# drv.net
KiCad netlist of a schematic drawn in Altium Designer
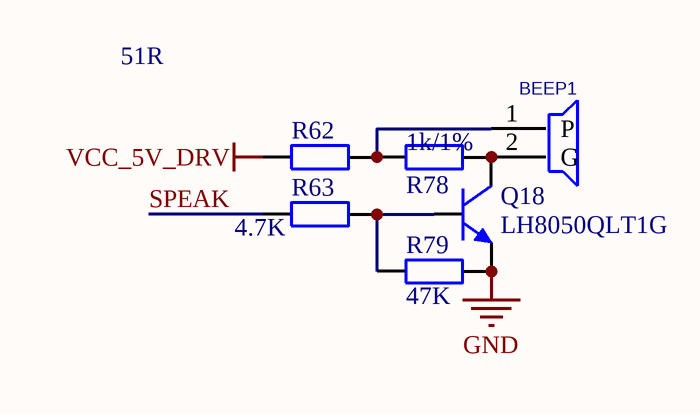
[diagram p0: drv.SchDoc]

(export (version "E")
  (design (tool "Eeschema 10.0.6"))
  (components
    (comp (ref "BEEP1")
      (value "BEEP-9.5X5.5")
      (footprint "BEEP-9.5X5.5")
      (libsource (lib "MINI-V3") (part "BEEP-9.5X5.5"))
    )
    (comp (ref "Q18")
      (value "LH8050QLT1G")
      (footprint "SOT-23")
      (description "NPN")
      (libsource (lib "XiaoyI") (part "NPN-1"))
    )
    (comp (ref "R62")
      (value "51R")
      (footprint "0603R")
      (description "贴片电阻 5%")
      (libsource (lib "") (part "RES0_1"))
    )
    (comp (ref "R63")
      (value "4.7K")
      (footprint "0603R")
      (description "贴片电阻 5%")
      (libsource (lib "ABB") (part "RES0"))
    )
    (comp (ref "R78")
      (value "1k/1%")
      (footprint "0603R")
      (description "贴片电阻 5%")
      (libsource (lib "") (part "RES0_1"))
    )
    (comp (ref "R79")
      (value "47K")
      (footprint "0603R")
      (description "贴片电阻 5%")
      (libsource (lib "ABB") (part "RES0"))
    )
  )
  (nets
    (net (code "1") (name "/SPEAK") (class "Default")
      (node (ref "R63") (pin "1") (pinfunction "1_1") (pintype "passive"))
    )
    (net (code "2") (name "GND") (class "Default")
      (node (ref "Q18") (pin "2") (pinfunction "E_2") (pintype "passive"))
      (node (ref "R79") (pin "2") (pinfunction "2_2") (pintype "passive"))
    )
    (net (code "3") (name "Net-(BEEP1-G)") (class "Default")
      (node (ref "BEEP1") (pin "2") (pinfunction "G_2") (pintype "passive"))
      (node (ref "Q18") (pin "3") (pinfunction "C_3") (pintype "passive"))
      (node (ref "R78") (pin "1") (pinfunction "1_1") (pintype "passive"))
    )
    (net (code "4") (name "Net-(BEEP1-P)") (class "Default")
      (node (ref "BEEP1") (pin "1") (pinfunction "P_1") (pintype "passive"))
      (node (ref "R62") (pin "1") (pinfunction "1_1") (pintype "passive"))
      (node (ref "R78") (pin "2") (pinfunction "2_2") (pintype "passive"))
    )
    (net (code "5") (name "Net-(Q18-B)") (class "Default")
      (node (ref "Q18") (pin "1") (pinfunction "B_1") (pintype "passive"))
      (node (ref "R63") (pin "2") (pinfunction "2_2") (pintype "passive"))
      (node (ref "R79") (pin "1") (pinfunction "1_1") (pintype "passive"))
    )
    (net (code "6") (name "VCC_5V_DRV") (class "Default")
      (node (ref "R62") (pin "2") (pinfunction "2_2") (pintype "passive"))
    )
  )
)
